# DM1098EMB_IO.net
KiCad netlist of a schematic drawn in Altium Designer
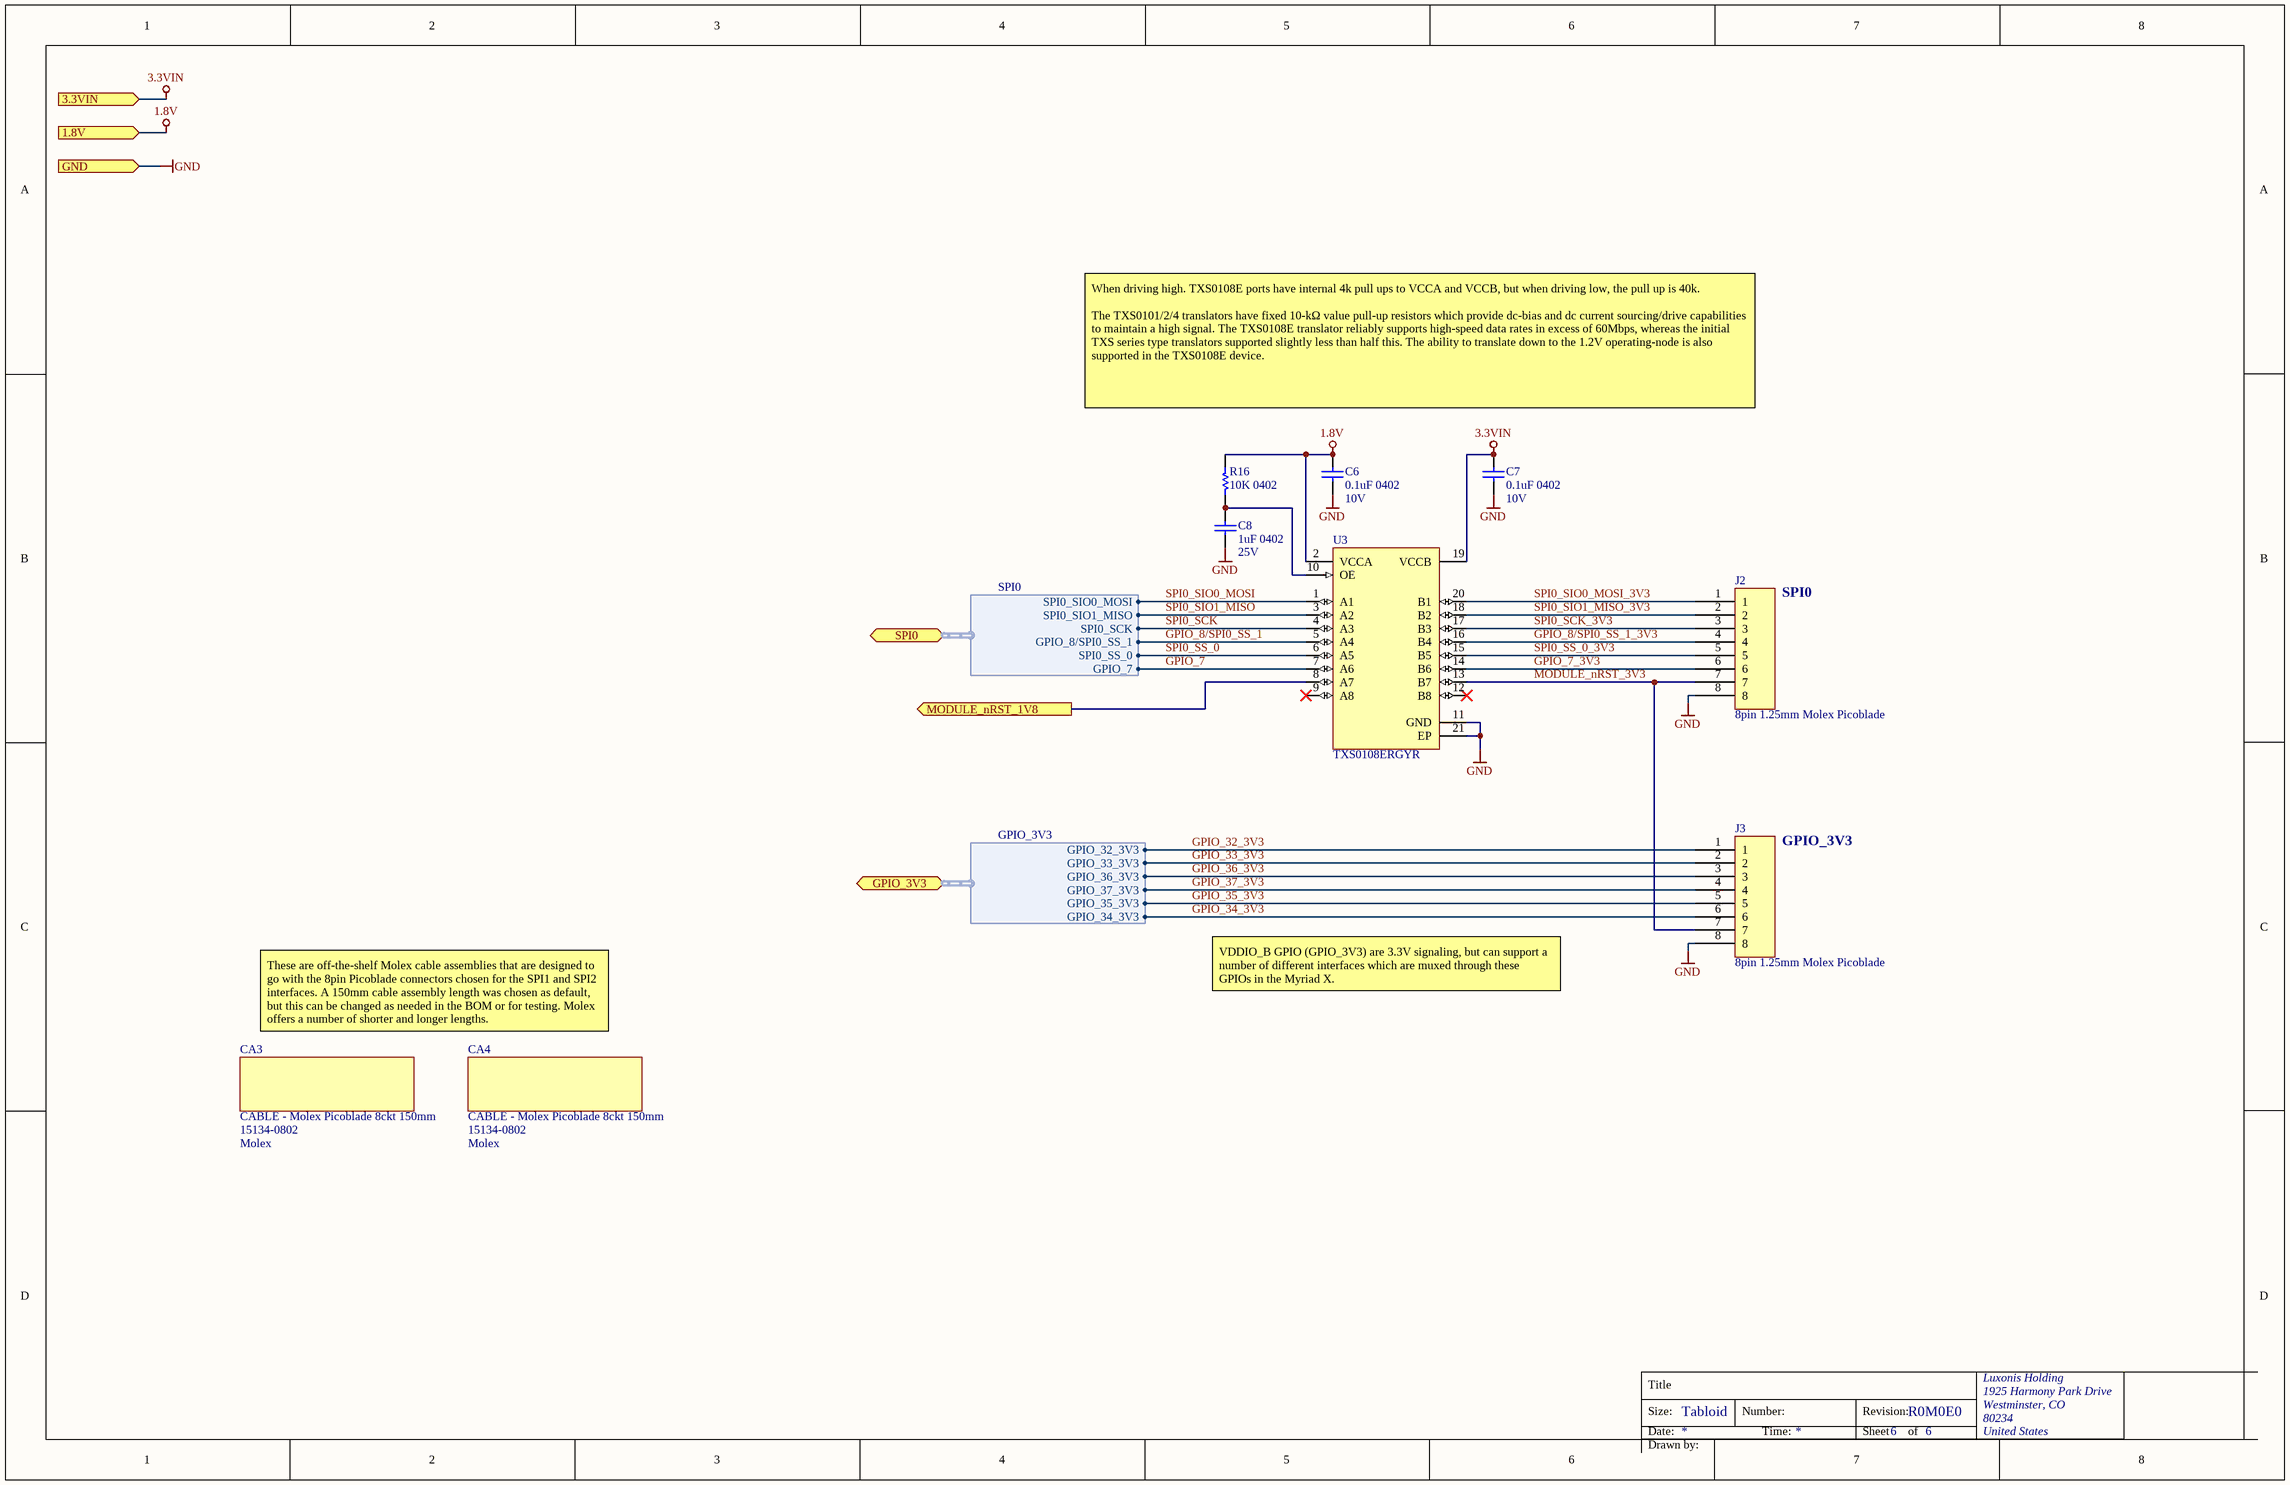
[diagram p0: DM1098EMB_IO.SchDoc]

(export (version "E")
  (design (tool "Eeschema 10.0.6"))
  (components
    (comp (ref "C6")
      (value "0.1uF 0402")
      (footprint "CAP_Altium_Vault_Generic:CAPC0402(1005)70_N")
      (description "CAP CER 0.1UF 10V X7R 0402 5%")
      (fields (field (name "TOLERANCE") "5%") (field (name "VOLTAGE RATING") "10V"))
      (libsource (lib "LuxonisMaster") (part "GRM155R71A104JA01D"))
    )
    (comp (ref "C7")
      (value "0.1uF 0402")
      (footprint "CAP_Altium_Vault_Generic:CAPC0402(1005)70_N")
      (description "CAP CER 0.1UF 10V X7R 0402 5%")
      (fields (field (name "TOLERANCE") "5%") (field (name "VOLTAGE RATING") "10V"))
      (libsource (lib "LuxonisMaster") (part "GRM155R71A104JA01D"))
    )
    (comp (ref "C8")
      (value "1uF 0402")
      (footprint "CAP_Altium_Vault_Generic:CAPC0402(1005)70_N")
      (description "CAP CER 1UF 25V X5R 0402 10%")
      (fields
        (field (name "TOLERANCE") "10%")
        (field (name "VOLTAGE") "25V")
        (field (name "VOLTAGE RATING") "25V")
      )
      (libsource (lib "LuxonisMaster") (part "GRM155R61E105KA12D"))
    )
    (comp (ref "CA3")
      (value "CABLE - Molex Picoblade 8ckt 150mm")
      (footprint "LuxonisMaster:15134-0802")
      (description "CABLE ASSY POWER CORD, 8P CRIMP SOCKET, 150MM, BLK")
      (fields
        (field (name "MANUFACTURER PART NUMBER 1") "15134-0802")
        (field (name "MANUFACTURER 1") "Molex")
      )
      (libsource (lib "LuxonisMaster") (part "15134-0802"))
    )
    (comp (ref "CA4")
      (value "CABLE - Molex Picoblade 8ckt 150mm")
      (footprint "LuxonisMaster:15134-0802")
      (description "CABLE ASSY POWER CORD, 8P CRIMP SOCKET, 150MM, BLK")
      (fields
        (field (name "MANUFACTURER PART NUMBER 1") "15134-0802")
        (field (name "MANUFACTURER 1") "Molex")
      )
      (libsource (lib "LuxonisMaster") (part "15134-0802"))
    )
    (comp (ref "J2")
      (value "8pin 1.25mm Molex Picoblade")
      (footprint "53047-0810")
      (description "CONN HEADER VERT 8POS 1.25MM  Connector Header Through Hole 8 position 0.049\" (1.25mm)")
      (libsource (lib "LuxonisMaster") (part "53047-0810"))
    )
    (comp (ref "J3")
      (value "8pin 1.25mm Molex Picoblade")
      (footprint "53047-0810")
      (description "CONN HEADER VERT 8POS 1.25MM  Connector Header Through Hole 8 position 0.049\" (1.25mm)")
      (libsource (lib "LuxonisMaster") (part "53047-0810"))
    )
    (comp (ref "R16")
      (value "10K 0402")
      (footprint "RES_Altium_Vault_Generic:RESC0402(1005)_N")
      (fields (field (name "TOLERANCE") "1%"))
      (libsource (lib "LuxonisMaster") (part "RC0402FR-1310KL"))
    )
    (comp (ref "U3")
      (value "TXS0108ERGYR")
      (footprint "LuxonisMaster:TXS0108ERGYR")
      (description "IC TRNSLTR BIDIRECTIONAL 20VQFN")
      (libsource (lib "LuxonisMaster") (part "TXS0108ERGYR"))
    )
  )
  (nets
    (net (code "3") (name "/GPIO_7") (class "Default")
      (node (ref "U3") (pin "7") (pinfunction "A6_7") (pintype "bidirectional"))
    )
    (net (code "4") (name "/GPIO_7_3V3") (class "Default")
      (node (ref "J2") (pin "6") (pinfunction "6_6") (pintype "passive"))
      (node (ref "U3") (pin "14") (pinfunction "B6_14") (pintype "bidirectional"))
    )
    (net (code "5") (name "/GPIO_8{slash}SPI0_SS_1") (class "Default")
      (node (ref "U3") (pin "5") (pinfunction "A4_5") (pintype "bidirectional"))
    )
    (net (code "6") (name "/GPIO_8{slash}SPI0_SS_1_3V3") (class "Default")
      (node (ref "J2") (pin "4") (pinfunction "4_4") (pintype "passive"))
      (node (ref "U3") (pin "16") (pinfunction "B4_16") (pintype "bidirectional"))
    )
    (net (code "7") (name "/GPIO_32_3V3") (class "Default")
      (node (ref "J3") (pin "1") (pinfunction "1_1") (pintype "passive"))
    )
    (net (code "8") (name "/GPIO_33_3V3") (class "Default")
      (node (ref "J3") (pin "2") (pinfunction "2_2") (pintype "passive"))
    )
    (net (code "9") (name "/GPIO_34_3V3") (class "Default")
      (node (ref "J3") (pin "6") (pinfunction "6_6") (pintype "passive"))
    )
    (net (code "10") (name "/GPIO_35_3V3") (class "Default")
      (node (ref "J3") (pin "5") (pinfunction "5_5") (pintype "passive"))
    )
    (net (code "11") (name "/GPIO_36_3V3") (class "Default")
      (node (ref "J3") (pin "3") (pinfunction "3_3") (pintype "passive"))
    )
    (net (code "12") (name "/GPIO_37_3V3") (class "Default")
      (node (ref "J3") (pin "4") (pinfunction "4_4") (pintype "passive"))
    )
    (net (code "13") (name "/MODULE_nRST_1V8") (class "Default")
      (node (ref "U3") (pin "8") (pinfunction "A7_8") (pintype "bidirectional"))
    )
    (net (code "14") (name "/MODULE_nRST_3V3") (class "Default")
      (node (ref "J2") (pin "7") (pinfunction "7_7") (pintype "passive"))
      (node (ref "J3") (pin "7") (pinfunction "7_7") (pintype "passive"))
      (node (ref "U3") (pin "13") (pinfunction "B7_13") (pintype "bidirectional"))
    )
    (net (code "15") (name "/SPI0_SCK") (class "Default")
      (node (ref "U3") (pin "4") (pinfunction "A3_4") (pintype "bidirectional"))
    )
    (net (code "16") (name "/SPI0_SCK_3V3") (class "Default")
      (node (ref "J2") (pin "3") (pinfunction "3_3") (pintype "passive"))
      (node (ref "U3") (pin "17") (pinfunction "B3_17") (pintype "bidirectional"))
    )
    (net (code "17") (name "/SPI0_SIO0_MOSI") (class "Default")
      (node (ref "U3") (pin "1") (pinfunction "A1_1") (pintype "bidirectional"))
    )
    (net (code "18") (name "/SPI0_SIO0_MOSI_3V3") (class "Default")
      (node (ref "J2") (pin "1") (pinfunction "1_1") (pintype "passive"))
      (node (ref "U3") (pin "20") (pinfunction "B1_20") (pintype "bidirectional"))
    )
    (net (code "19") (name "/SPI0_SIO1_MISO") (class "Default")
      (node (ref "U3") (pin "3") (pinfunction "A2_3") (pintype "bidirectional"))
    )
    (net (code "20") (name "/SPI0_SIO1_MISO_3V3") (class "Default")
      (node (ref "J2") (pin "2") (pinfunction "2_2") (pintype "passive"))
      (node (ref "U3") (pin "18") (pinfunction "B2_18") (pintype "bidirectional"))
    )
    (net (code "21") (name "/SPI0_SS_0") (class "Default")
      (node (ref "U3") (pin "6") (pinfunction "A5_6") (pintype "bidirectional"))
    )
    (net (code "22") (name "/SPI0_SS_0_3V3") (class "Default")
      (node (ref "J2") (pin "5") (pinfunction "5_5") (pintype "passive"))
      (node (ref "U3") (pin "15") (pinfunction "B5_15") (pintype "bidirectional"))
    )
    (net (code "25") (name "1.8V") (class "Default")
      (node (ref "C6") (pin "2") (pinfunction "2_2") (pintype "passive"))
      (node (ref "R16") (pin "1") (pinfunction "1_1") (pintype "passive"))
      (node (ref "U3") (pin "2") (pinfunction "VCCA_2") (pintype "power_in"))
    )
    (net (code "26") (name "3.3VIN") (class "Default")
      (node (ref "C7") (pin "2") (pinfunction "2_2") (pintype "passive"))
      (node (ref "U3") (pin "19") (pinfunction "VCCB_19") (pintype "power_in"))
    )
    (net (code "27") (name "GND") (class "Default")
      (node (ref "C6") (pin "1") (pinfunction "1_1") (pintype "passive"))
      (node (ref "C7") (pin "1") (pinfunction "1_1") (pintype "passive"))
      (node (ref "C8") (pin "1") (pinfunction "1_1") (pintype "passive"))
      (node (ref "J2") (pin "8") (pinfunction "8_8") (pintype "passive"))
      (node (ref "J3") (pin "8") (pinfunction "8_8") (pintype "passive"))
      (node (ref "U3") (pin "11") (pinfunction "GND_11") (pintype "power_in"))
      (node (ref "U3") (pin "21") (pinfunction "EP_21") (pintype "power_in"))
    )
    (net (code "28") (name "Net-(U3-OE)") (class "Default")
      (node (ref "C8") (pin "2") (pinfunction "2_2") (pintype "passive"))
      (node (ref "R16") (pin "2") (pinfunction "2_2") (pintype "passive"))
      (node (ref "U3") (pin "10") (pinfunction "OE_10") (pintype "input"))
    )
    (net (code "29") (name "unconnected-(U3-A8-Pad9)") (class "Default")
      (node (ref "U3") (pin "9") (pinfunction "A8_9") (pintype "bidirectional+no_connect"))
    )
    (net (code "30") (name "unconnected-(U3-B8-Pad12)") (class "Default")
      (node (ref "U3") (pin "12") (pinfunction "B8_12") (pintype "bidirectional+no_connect"))
    )
  )
)
